# floppy_m0dule.net
KiCad netlist of a schematic drawn in Altium Designer
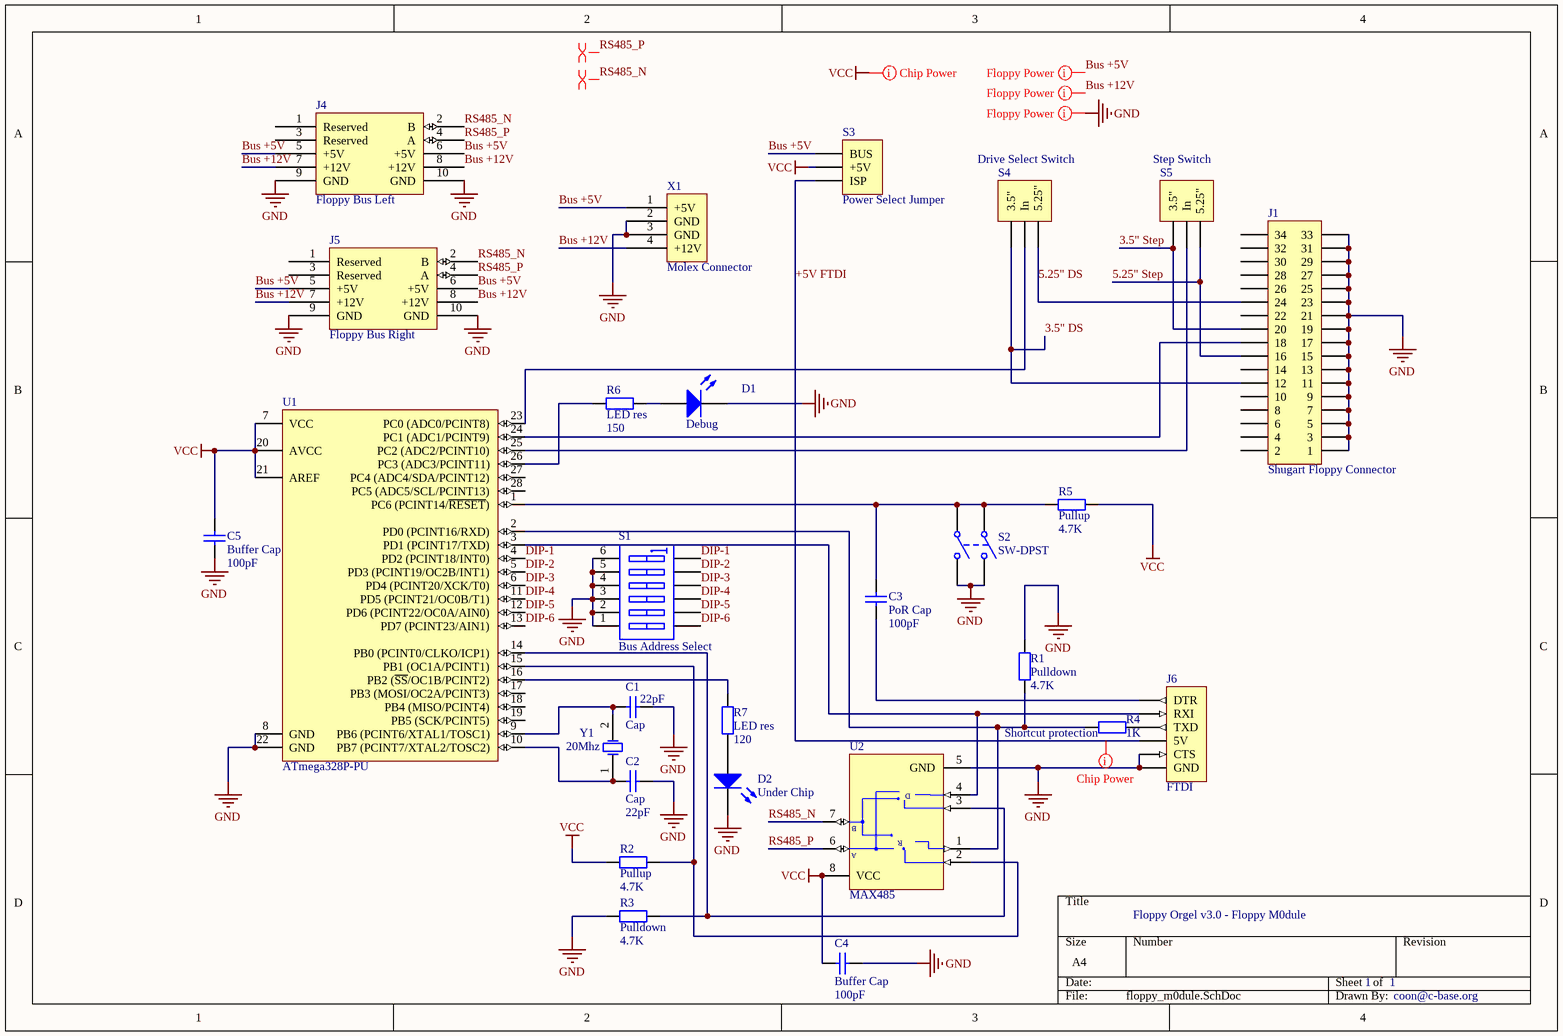
[diagram p0: floppy_m0dule.SchDoc]

(export (version "E")
  (design (tool "Eeschema 10.0.6"))
  (components
    (comp (ref "C1")
      (value "Cap")
      (footprint "RAD-0.1")
      (description "Capacitor")
      (fields (field (name "ALTIUM_VALUE") "22pF") (field (name "PUBLISHER") "Altium Limited"))
      (libsource (lib "Miscellaneous Devices") (part "Cap"))
    )
    (comp (ref "C2")
      (value "Cap")
      (footprint "RAD-0.1")
      (description "Capacitor")
      (fields (field (name "ALTIUM_VALUE") "22pF") (field (name "PUBLISHER") "Altium Limited"))
      (libsource (lib "Miscellaneous Devices") (part "Cap"))
    )
    (comp (ref "C3")
      (value "PoR Cap")
      (footprint "RAD-0.1")
      (description "Capacitor")
      (fields (field (name "ALTIUM_VALUE") "100pF") (field (name "PUBLISHER") "Altium Limited"))
      (libsource (lib "Miscellaneous Devices") (part "Cap"))
    )
    (comp (ref "C4")
      (value "Buffer Cap")
      (footprint "C1206")
      (description "Capacitor (Semiconductor SIM Model)")
      (fields (field (name "ALTIUM_VALUE") "100pF") (field (name "PUBLISHER") "Altium Limited"))
      (libsource (lib "Miscellaneous Devices") (part "Cap Semi"))
    )
    (comp (ref "C5")
      (value "Buffer Cap")
      (footprint "C1206")
      (description "Capacitor (Semiconductor SIM Model)")
      (fields (field (name "ALTIUM_VALUE") "100pF") (field (name "PUBLISHER") "Altium Limited"))
      (libsource (lib "Miscellaneous Devices") (part "Cap Semi"))
    )
    (comp (ref "D1")
      (value "Debug")
      (footprint "0805 LED")
      (description "Typical BLUE SiC LED")
      (fields (field (name "PUBLISHER") "Altium Limited"))
      (libsource (lib "Miscellaneous Devices") (part "LED3"))
    )
    (comp (ref "D2")
      (value "Under Chip")
      (footprint "0805 LED")
      (description "Typical BLUE SiC LED")
      (fields (field (name "PUBLISHER") "Altium Limited"))
      (libsource (lib "Miscellaneous Devices") (part "LED3"))
    )
    (comp (ref "J1")
      (value "Shugart Floppy Connector")
      (footprint "HDR2X17")
      (description "Header, 17-Pin, Dual row")
      (fields (field (name "PUBLISHER") "Altium Limited"))
      (libsource (lib "Miscellaneous Connectors") (part "Header 17X2"))
    )
    (comp (ref "J4")
      (value "Floppy Bus Left")
      (footprint "Shrouded Pinheader 2x5")
      (description "10 Pin Floppy bus connector for rainbow cable")
      (fields (field (name "PUBLISHER") "Altium Limited"))
      (libsource (lib "floppyorgel") (part "Floppy Bus Connector"))
    )
    (comp (ref "J5")
      (value "Floppy Bus Right")
      (footprint "Shrouded Pinheader 2x5")
      (description "10 Pin Floppy bus connector for rainbow cable")
      (fields (field (name "PUBLISHER") "Altium Limited"))
      (libsource (lib "floppyorgel") (part "Floppy Bus Connector"))
    )
    (comp (ref "J6")
      (value "FTDI")
      (footprint "HDR1X6")
      (description "Header, 6-Pin")
      (fields (field (name "PUBLISHER") "Altium Limited"))
      (libsource (lib "Miscellaneous Connectors") (part "Header 6"))
    )
    (comp (ref "R1")
      (value "Pulldown")
      (footprint "AXIAL-0.4")
      (description "Resistor")
      (fields (field (name "ALTIUM_VALUE") "4.7K") (field (name "PUBLISHER") "Altium Limited"))
      (libsource (lib "") (part "Res2_1"))
    )
    (comp (ref "R2")
      (value "Pullup")
      (footprint "AXIAL-0.4")
      (description "Resistor")
      (fields (field (name "ALTIUM_VALUE") "4.7K") (field (name "PUBLISHER") "Altium Limited"))
      (libsource (lib "Miscellaneous Devices") (part "Res2"))
    )
    (comp (ref "R3")
      (value "Pulldown")
      (footprint "AXIAL-0.4")
      (description "Resistor")
      (fields (field (name "ALTIUM_VALUE") "4.7K") (field (name "PUBLISHER") "Altium Limited"))
      (libsource (lib "Miscellaneous Devices") (part "Res2"))
    )
    (comp (ref "R4")
      (value "Shortcut protection")
      (footprint "AXIAL-0.4")
      (description "Resistor")
      (fields (field (name "ALTIUM_VALUE") "1K") (field (name "PUBLISHER") "Altium Limited"))
      (libsource (lib "Miscellaneous Devices") (part "Res2"))
    )
    (comp (ref "R5")
      (value "Pullup")
      (footprint "AXIAL-0.4")
      (description "Resistor")
      (fields (field (name "ALTIUM_VALUE") "4.7K") (field (name "PUBLISHER") "Altium Limited"))
      (libsource (lib "Miscellaneous Devices") (part "Res2"))
    )
    (comp (ref "R6")
      (value "LED res")
      (footprint "R0805")
      (description "Resistor for Green LED 19.33mA @ 5V")
      (fields (field (name "ALTIUM_VALUE") "150") (field (name "PUBLISHER") "Altium Limited"))
      (libsource (lib "Miscellaneous Devices") (part "Res2"))
    )
    (comp (ref "R7")
      (value "LED res")
      (footprint "R0805")
      (description "Resistor for Blue LED 17.5mA @ 5V")
      (fields (field (name "ALTIUM_VALUE") "120") (field (name "PUBLISHER") "Altium Limited"))
      (libsource (lib "") (part "Res2_1"))
    )
    (comp (ref "S1")
      (value "Bus Address Select")
      (footprint "418117170906")
      (description "Midi Channel Select")
      (fields (field (name "PUBLISHER") "Altium Limited"))
      (libsource (lib "Miscellaneous Devices") (part "SW DIP-6"))
    )
    (comp (ref "S2")
      (value "SW-DPST")
      (footprint "SWITCH")
      (description "Double-Pole, Single-Throw Switch")
      (fields (field (name "PUBLISHER") "Altium Limited"))
      (libsource (lib "Miscellaneous Devices") (part "SW-DPST"))
    )
    (comp (ref "S3")
      (value "Power Select Jumper")
      (footprint "HDR1X3")
      (description "Header, 3-Pin, Right Angle")
      (fields (field (name "PUBLISHER") "Altium Limited"))
      (libsource (lib "Miscellaneous Connectors") (part "Header 3H"))
    )
    (comp (ref "S4")
      (value "Drive Select Switch")
      (footprint "0805 SMD Switch Pads")
      (description "Header, 3-Pin")
      (fields (field (name "PUBLISHER") "Altium Limited"))
      (libsource (lib "Miscellaneous Connectors") (part "Header 3"))
    )
    (comp (ref "S5")
      (value "Step Switch")
      (footprint "0805 SMD Switch Pads")
      (description "Header, 3-Pin")
      (fields (field (name "PUBLISHER") "Altium Limited"))
      (libsource (lib "Miscellaneous Connectors") (part "Header 3"))
    )
    (comp (ref "U1")
      (value "ATmega328P-PU")
      (footprint "28P3")
      (fields (field (name "PUBLISHER") "Altium Limited"))
      (libsource (lib "Atmel Microcontroller 8-Bit megaAVR") (part "ATmega328P-PU"))
    )
    (comp (ref "U2")
      (value "MAX485")
      (footprint "PA8")
      (description "Low-Power, Slew-Rate-Limited RS-485/RS-422 Transceiver")
      (fields (field (name "PUBLISHER") "Altium Limited"))
      (libsource (lib "Maxim Communication Transceiver") (part "MAX485EPA"))
    )
    (comp (ref "X1")
      (value "Molex Connector")
      (footprint "HDR1X4")
      (description "Molex Power Supply Connector")
      (fields (field (name "PUBLISHER") "Altium Limited"))
      (libsource (lib "floppyorgel") (part "Molex Connector"))
    )
    (comp (ref "Y1")
      (value "20Mhz")
      (footprint "crystal")
      (description "Crystal Oscillator")
      (fields (field (name "PUBLISHER") "Altium Limited"))
      (libsource (lib "Miscellaneous Devices") (part "XTAL"))
    )
  )
  (nets
    (net (code "1") (name "/+5V FTDI") (class "Default")
      (node (ref "J6") (pin "4") (pinfunction "5V_4") (pintype "power_in"))
      (node (ref "S3") (pin "3") (pinfunction "ISP_3") (pintype "power_in"))
    )
    (net (code "2") (name "/3.5\" DS") (class "Default")
      (node (ref "J1") (pin "12") (pinfunction "12_12") (pintype "passive"))
      (node (ref "S4") (pin "1") (pinfunction "3.5\"_1") (pintype "passive"))
    )
    (net (code "3") (name "/3.5\" Step") (class "Default")
      (node (ref "J1") (pin "20") (pinfunction "20_20") (pintype "passive"))
      (node (ref "S5") (pin "1") (pinfunction "3.5\"_1") (pintype "passive"))
    )
    (net (code "4") (name "/5.25\" DS") (class "Default")
      (node (ref "J1") (pin "24") (pinfunction "24_24") (pintype "passive"))
      (node (ref "S4") (pin "3") (pinfunction "5.25\"_3") (pintype "passive"))
    )
    (net (code "5") (name "/5.25\" Step") (class "Default")
      (node (ref "J1") (pin "16") (pinfunction "16_16") (pintype "passive"))
      (node (ref "S5") (pin "3") (pinfunction "5.25\"_3") (pintype "passive"))
    )
    (net (code "6") (name "/Bus +5V") (class "Default")
      (node (ref "J4") (pin "5") (pinfunction "+5V_5") (pintype "passive"))
      (node (ref "J4") (pin "6") (pinfunction "+5V_6") (pintype "power_in"))
      (node (ref "J5") (pin "5") (pinfunction "+5V_5") (pintype "passive"))
      (node (ref "J5") (pin "6") (pinfunction "+5V_6") (pintype "power_in"))
      (node (ref "S3") (pin "1") (pinfunction "BUS_1") (pintype "power_in"))
      (node (ref "X1") (pin "1") (pinfunction "+5V_1") (pintype "power_in"))
    )
    (net (code "7") (name "/Bus +12V") (class "Default")
      (node (ref "J4") (pin "7") (pinfunction "+12V_7") (pintype "passive"))
      (node (ref "J4") (pin "8") (pinfunction "+12V_8") (pintype "power_in"))
      (node (ref "J5") (pin "7") (pinfunction "+12V_7") (pintype "passive"))
      (node (ref "J5") (pin "8") (pinfunction "+12V_8") (pintype "power_in"))
      (node (ref "X1") (pin "4") (pinfunction "+12V_4") (pintype "power_in"))
    )
    (net (code "8") (name "/DIP-1") (class "Default")
      (node (ref "S1") (pin "12") (pinfunction "B1_12") (pintype "passive"))
      (node (ref "U1") (pin "4") (pinfunction "PD2_(PCINT18/INT0)_4") (pintype "bidirectional"))
    )
    (net (code "9") (name "/DIP-2") (class "Default")
      (node (ref "S1") (pin "11") (pinfunction "B2_11") (pintype "passive"))
      (node (ref "U1") (pin "5") (pinfunction "PD3_(PCINT19/OC2B/INT1)_5") (pintype "bidirectional"))
    )
    (net (code "10") (name "/DIP-3") (class "Default")
      (node (ref "S1") (pin "10") (pinfunction "B3_10") (pintype "passive"))
      (node (ref "U1") (pin "6") (pinfunction "PD4_(PCINT20/XCK/T0)_6") (pintype "bidirectional"))
    )
    (net (code "11") (name "/DIP-4") (class "Default")
      (node (ref "S1") (pin "9") (pinfunction "B4_9") (pintype "passive"))
      (node (ref "U1") (pin "11") (pinfunction "PD5_(PCINT21/OC0B/T1)_11") (pintype "bidirectional"))
    )
    (net (code "12") (name "/DIP-5") (class "Default")
      (node (ref "S1") (pin "8") (pinfunction "B5_8") (pintype "passive"))
      (node (ref "U1") (pin "12") (pinfunction "PD6_(PCINT22/OC0A/AIN0)_12") (pintype "bidirectional"))
    )
    (net (code "13") (name "/DIP-6") (class "Default")
      (node (ref "S1") (pin "7") (pinfunction "B6_7") (pintype "passive"))
      (node (ref "U1") (pin "13") (pinfunction "PD7_(PCINT23/AIN1)_13") (pintype "bidirectional"))
    )
    (net (code "14") (name "/RS485_N") (class "Default")
      (node (ref "J4") (pin "2") (pinfunction "B_2") (pintype "bidirectional"))
      (node (ref "J5") (pin "2") (pinfunction "B_2") (pintype "bidirectional"))
      (node (ref "U2") (pin "7") (pinfunction "B_7") (pintype "bidirectional"))
    )
    (net (code "15") (name "/RS485_P") (class "Default")
      (node (ref "J4") (pin "4") (pinfunction "A_4") (pintype "bidirectional"))
      (node (ref "J5") (pin "4") (pinfunction "A_4") (pintype "bidirectional"))
      (node (ref "U2") (pin "6") (pinfunction "A_6") (pintype "bidirectional"))
    )
    (net (code "16") (name "GND") (class "Default")
      (node (ref "C1") (pin "2") (pinfunction "2_2") (pintype "passive"))
      (node (ref "C2") (pin "2") (pinfunction "2_2") (pintype "passive"))
      (node (ref "C4") (pin "1") (pinfunction "1_1") (pintype "passive"))
      (node (ref "C5") (pin "1") (pinfunction "1_1") (pintype "passive"))
      (node (ref "D1") (pin "2") (pinfunction "K_2") (pintype "passive"))
      (node (ref "D2") (pin "2") (pinfunction "K_2") (pintype "passive"))
      (node (ref "J1") (pin "1") (pinfunction "1_1") (pintype "passive"))
      (node (ref "J1") (pin "11") (pinfunction "11_11") (pintype "passive"))
      (node (ref "J1") (pin "13") (pinfunction "13_13") (pintype "passive"))
      (node (ref "J1") (pin "15") (pinfunction "15_15") (pintype "passive"))
      (node (ref "J1") (pin "17") (pinfunction "17_17") (pintype "passive"))
      (node (ref "J1") (pin "19") (pinfunction "19_19") (pintype "passive"))
      (node (ref "J1") (pin "21") (pinfunction "21_21") (pintype "passive"))
      (node (ref "J1") (pin "23") (pinfunction "23_23") (pintype "passive"))
      (node (ref "J1") (pin "25") (pinfunction "25_25") (pintype "passive"))
      (node (ref "J1") (pin "27") (pinfunction "27_27") (pintype "passive"))
      (node (ref "J1") (pin "29") (pinfunction "29_29") (pintype "passive"))
      (node (ref "J1") (pin "3") (pinfunction "3_3") (pintype "passive"))
      (node (ref "J1") (pin "31") (pinfunction "31_31") (pintype "passive"))
      (node (ref "J1") (pin "33") (pinfunction "33_33") (pintype "passive"))
      (node (ref "J1") (pin "5") (pinfunction "5_5") (pintype "passive"))
      (node (ref "J1") (pin "7") (pinfunction "7_7") (pintype "passive"))
      (node (ref "J1") (pin "9") (pinfunction "9_9") (pintype "passive"))
      (node (ref "J4") (pin "10") (pinfunction "GND_10") (pintype "passive"))
      (node (ref "J4") (pin "9") (pinfunction "GND_9") (pintype "power_in"))
      (node (ref "J5") (pin "10") (pinfunction "GND_10") (pintype "passive"))
      (node (ref "J5") (pin "9") (pinfunction "GND_9") (pintype "power_in"))
      (node (ref "J6") (pin "5") (pinfunction "CTS_5") (pintype "input"))
      (node (ref "J6") (pin "6") (pinfunction "GND_6") (pintype "power_in"))
      (node (ref "R1") (pin "2") (pinfunction "2_2") (pintype "passive"))
      (node (ref "R3") (pin "1") (pinfunction "1_1") (pintype "passive"))
      (node (ref "S1") (pin "1") (pinfunction "A1_1") (pintype "passive"))
      (node (ref "S1") (pin "2") (pinfunction "A2_2") (pintype "passive"))
      (node (ref "S1") (pin "3") (pinfunction "A3_3") (pintype "passive"))
      (node (ref "S1") (pin "4") (pinfunction "A4_4") (pintype "passive"))
      (node (ref "S1") (pin "5") (pinfunction "A5_5") (pintype "passive"))
      (node (ref "S1") (pin "6") (pinfunction "A6_6") (pintype "passive"))
      (node (ref "S2") (pin "2") (pinfunction "NO1_2") (pintype "passive"))
      (node (ref "S2") (pin "4") (pinfunction "NO2_4") (pintype "passive"))
      (node (ref "U1") (pin "22") (pinfunction "GND_22") (pintype "power_in"))
      (node (ref "U1") (pin "8") (pinfunction "GND_8") (pintype "power_in"))
      (node (ref "U2") (pin "5") (pinfunction "GND_5") (pintype "power_in"))
      (node (ref "X1") (pin "2") (pinfunction "GND_2") (pintype "power_in"))
      (node (ref "X1") (pin "3") (pinfunction "GND_3") (pintype "power_in"))
    )
    (net (code "17") (name "Net-(D1-A)") (class "Default")
      (node (ref "D1") (pin "1") (pinfunction "A_1") (pintype "passive"))
      (node (ref "R6") (pin "2") (pinfunction "2_2") (pintype "passive"))
    )
    (net (code "18") (name "Net-(D2-A)") (class "Default")
      (node (ref "D2") (pin "1") (pinfunction "A_1") (pintype "passive"))
      (node (ref "R7") (pin "1") (pinfunction "1_1") (pintype "passive"))
    )
    (net (code "19") (name "Net-(J6-DTR)") (class "Default")
      (node (ref "C3") (pin "1") (pinfunction "1_1") (pintype "passive"))
      (node (ref "J6") (pin "1") (pinfunction "DTR_1") (pintype "output"))
    )
    (net (code "20") (name "Net-(J6-RXI)") (class "Default")
      (node (ref "J6") (pin "2") (pinfunction "RXI_2") (pintype "input"))
      (node (ref "U1") (pin "3") (pinfunction "PD1_(PCINT17/TXD)_3") (pintype "bidirectional"))
      (node (ref "U2") (pin "4") (pinfunction "DI_4") (pintype "input"))
    )
    (net (code "21") (name "Net-(J6-TXD)") (class "Default")
      (node (ref "J6") (pin "3") (pinfunction "TXD_3") (pintype "output"))
      (node (ref "R4") (pin "2") (pinfunction "2_2") (pintype "passive"))
    )
    (net (code "22") (name "Net-(S2-COMMON1)") (class "Default")
      (node (ref "C3") (pin "2") (pinfunction "2_2") (pintype "passive"))
      (node (ref "R5") (pin "1") (pinfunction "1_1") (pintype "passive"))
      (node (ref "S2") (pin "1") (pinfunction "COMMON1_1") (pintype "passive"))
      (node (ref "S2") (pin "3") (pinfunction "COMMON2_3") (pintype "passive"))
      (node (ref "U1") (pin "1") (pinfunction "PC6_(PCINT14/~{RESET})_1") (pintype "bidirectional"))
    )
    (net (code "23") (name "Net-(S4-In)") (class "Default")
      (node (ref "S4") (pin "2") (pinfunction "In_2") (pintype "passive"))
      (node (ref "U1") (pin "23") (pinfunction "PC0_(ADC0/PCINT8)_23") (pintype "bidirectional"))
    )
    (net (code "24") (name "Net-(S5-In)") (class "Default")
      (node (ref "S5") (pin "2") (pinfunction "In_2") (pintype "passive"))
      (node (ref "U1") (pin "25") (pinfunction "PC2_(ADC2/PCINT10)_25") (pintype "bidirectional"))
    )
    (net (code "25") (name "Net-(U1-PB0_(PCINT0{slash}CLKO{slash}ICP1))") (class "Default")
      (node (ref "R3") (pin "2") (pinfunction "2_2") (pintype "passive"))
      (node (ref "U1") (pin "14") (pinfunction "PB0_(PCINT0/CLKO/ICP1)_14") (pintype "bidirectional"))
      (node (ref "U2") (pin "3") (pinfunction "DE_3") (pintype "input"))
    )
    (net (code "26") (name "Net-(U1-PB1_(OC1A{slash}PCINT1))") (class "Default")
      (node (ref "R2") (pin "2") (pinfunction "2_2") (pintype "passive"))
      (node (ref "U1") (pin "15") (pinfunction "PB1_(OC1A/PCINT1)_15") (pintype "bidirectional"))
      (node (ref "U2") (pin "2") (pinfunction "~{RE}_2") (pintype "input"))
    )
    (net (code "27") (name "Net-(U1-PB2_(~{SS}{slash}OC1B{slash}PCINT2))") (class "Default")
      (node (ref "R7") (pin "2") (pinfunction "2_2") (pintype "passive"))
      (node (ref "U1") (pin "16") (pinfunction "PB2_(~{SS}/OC1B/PCINT2)_16") (pintype "bidirectional"))
    )
    (net (code "28") (name "Net-(U1-PB6_(PCINT6{slash}XTAL1{slash}TOSC1))") (class "Default")
      (node (ref "C1") (pin "1") (pinfunction "1_1") (pintype "passive"))
      (node (ref "U1") (pin "9") (pinfunction "PB6_(PCINT6/XTAL1/TOSC1)_9") (pintype "bidirectional"))
      (node (ref "Y1") (pin "2") (pinfunction "OSC2_2") (pintype "passive"))
    )
    (net (code "29") (name "Net-(U1-PB7_(PCINT7{slash}XTAL2{slash}TOSC2))") (class "Default")
      (node (ref "C2") (pin "1") (pinfunction "1_1") (pintype "passive"))
      (node (ref "U1") (pin "10") (pinfunction "PB7_(PCINT7/XTAL2/TOSC2)_10") (pintype "bidirectional"))
      (node (ref "Y1") (pin "1") (pinfunction "OSC1_1") (pintype "passive"))
    )
    (net (code "30") (name "Net-(U1-PC1_(ADC1{slash}PCINT9))") (class "Default")
      (node (ref "J1") (pin "18") (pinfunction "18_18") (pintype "passive"))
      (node (ref "U1") (pin "24") (pinfunction "PC1_(ADC1/PCINT9)_24") (pintype "bidirectional"))
    )
    (net (code "31") (name "Net-(U1-PC3_(ADC3{slash}PCINT11))") (class "Default")
      (node (ref "R6") (pin "1") (pinfunction "1_1") (pintype "passive"))
      (node (ref "U1") (pin "26") (pinfunction "PC3_(ADC3/PCINT11)_26") (pintype "bidirectional"))
    )
    (net (code "32") (name "Net-(U1-PD0_(PCINT16{slash}RXD))") (class "Default")
      (node (ref "R1") (pin "1") (pinfunction "1_1") (pintype "passive"))
      (node (ref "R4") (pin "1") (pinfunction "1_1") (pintype "passive"))
      (node (ref "U1") (pin "2") (pinfunction "PD0_(PCINT16/RXD)_2") (pintype "bidirectional"))
      (node (ref "U2") (pin "1") (pinfunction "RO_1") (pintype "output"))
    )
    (net (code "33") (name "VCC") (class "Default")
      (node (ref "C4") (pin "2") (pinfunction "2_2") (pintype "passive"))
      (node (ref "C5") (pin "2") (pinfunction "2_2") (pintype "passive"))
      (node (ref "R2") (pin "1") (pinfunction "1_1") (pintype "passive"))
      (node (ref "R5") (pin "2") (pinfunction "2_2") (pintype "passive"))
      (node (ref "S3") (pin "2") (pinfunction "+5V_2") (pintype "power_in"))
      (node (ref "U1") (pin "20") (pinfunction "AVCC_20") (pintype "power_in"))
      (node (ref "U1") (pin "21") (pinfunction "AREF_21") (pintype "power_in"))
      (node (ref "U1") (pin "7") (pinfunction "VCC_7") (pintype "power_in"))
      (node (ref "U2") (pin "8") (pinfunction "VCC_8") (pintype "power_in"))
    )
    (net (code "34") (name "unconnected-(J1-Pad2)") (class "Default")
      (node (ref "J1") (pin "2") (pinfunction "2_2") (pintype "passive"))
    )
    (net (code "35") (name "unconnected-(J1-Pad4)") (class "Default")
      (node (ref "J1") (pin "4") (pinfunction "4_4") (pintype "passive"))
    )
    (net (code "36") (name "unconnected-(J1-Pad6)") (class "Default")
      (node (ref "J1") (pin "6") (pinfunction "6_6") (pintype "passive"))
    )
    (net (code "37") (name "unconnected-(J1-Pad8)") (class "Default")
      (node (ref "J1") (pin "8") (pinfunction "8_8") (pintype "passive"))
    )
    (net (code "38") (name "unconnected-(J1-Pad10)") (class "Default")
      (node (ref "J1") (pin "10") (pinfunction "10_10") (pintype "passive"))
    )
    (net (code "39") (name "unconnected-(J1-Pad14)") (class "Default")
      (node (ref "J1") (pin "14") (pinfunction "14_14") (pintype "passive"))
    )
    (net (code "40") (name "unconnected-(J1-Pad22)") (class "Default")
      (node (ref "J1") (pin "22") (pinfunction "22_22") (pintype "passive"))
    )
    (net (code "41") (name "unconnected-(J1-Pad26)") (class "Default")
      (node (ref "J1") (pin "26") (pinfunction "26_26") (pintype "passive"))
    )
    (net (code "42") (name "unconnected-(J1-Pad28)") (class "Default")
      (node (ref "J1") (pin "28") (pinfunction "28_28") (pintype "passive"))
    )
    (net (code "43") (name "unconnected-(J1-Pad30)") (class "Default")
      (node (ref "J1") (pin "30") (pinfunction "30_30") (pintype "passive"))
    )
    (net (code "44") (name "unconnected-(J1-Pad32)") (class "Default")
      (node (ref "J1") (pin "32") (pinfunction "32_32") (pintype "passive"))
    )
    (net (code "45") (name "unconnected-(J1-Pad34)") (class "Default")
      (node (ref "J1") (pin "34") (pinfunction "34_34") (pintype "passive"))
    )
    (net (code "46") (name "unconnected-(J4-Reserved-Pad1)") (class "Default")
      (node (ref "J4") (pin "1") (pinfunction "Reserved_1") (pintype "passive"))
    )
    (net (code "47") (name "unconnected-(J4-Reserved-Pad3)") (class "Default")
      (node (ref "J4") (pin "3") (pinfunction "Reserved_3") (pintype "passive"))
    )
    (net (code "48") (name "unconnected-(J5-Reserved-Pad1)") (class "Default")
      (node (ref "J5") (pin "1") (pinfunction "Reserved_1") (pintype "passive"))
    )
    (net (code "49") (name "unconnected-(J5-Reserved-Pad3)") (class "Default")
      (node (ref "J5") (pin "3") (pinfunction "Reserved_3") (pintype "passive"))
    )
    (net (code "50") (name "unconnected-(U1-PB3_(MOSI{slash}OC2A{slash}PCINT3)-Pad17)") (class "Default")
      (node (ref "U1") (pin "17") (pinfunction "PB3_(MOSI/OC2A/PCINT3)_17") (pintype "bidirectional"))
    )
    (net (code "51") (name "unconnected-(U1-PB4_(MISO{slash}PCINT4)-Pad18)") (class "Default")
      (node (ref "U1") (pin "18") (pinfunction "PB4_(MISO/PCINT4)_18") (pintype "bidirectional"))
    )
    (net (code "52") (name "unconnected-(U1-PB5_(SCK{slash}PCINT5)-Pad19)") (class "Default")
      (node (ref "U1") (pin "19") (pinfunction "PB5_(SCK/PCINT5)_19") (pintype "bidirectional"))
    )
    (net (code "53") (name "unconnected-(U1-PC4_(ADC4{slash}SDA{slash}PCINT12)-Pad27)") (class "Default")
      (node (ref "U1") (pin "27") (pinfunction "PC4_(ADC4/SDA/PCINT12)_27") (pintype "bidirectional"))
    )
    (net (code "54") (name "unconnected-(U1-PC5_(ADC5{slash}SCL{slash}PCINT13)-Pad28)") (class "Default")
      (node (ref "U1") (pin "28") (pinfunction "PC5_(ADC5/SCL/PCINT13)_28") (pintype "bidirectional"))
    )
  )
)
